# signalIsolator.net
KiCad netlist of a schematic drawn in Altium Designer
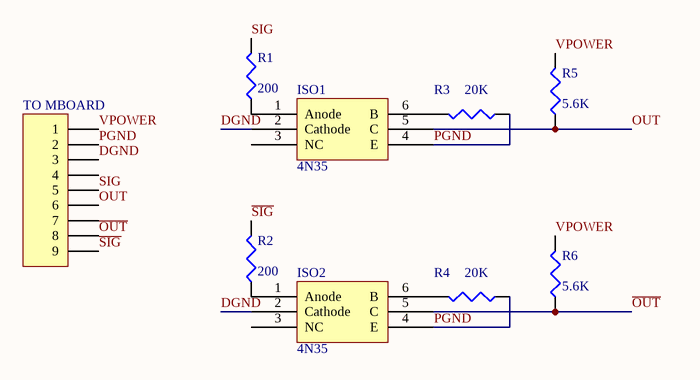
[diagram p0: signalIsolator.SchDoc]

(export (version "E")
  (design (tool "Eeschema 10.0.6"))
  (components
    (comp (ref "ISO1")
      (value "4N35")
      (footprint "DIP6LGE")
      (libsource (lib "controllerSchLib") (part "4N35"))
    )
    (comp (ref "ISO2")
      (value "4N35")
      (footprint "DIP6LGE")
      (libsource (lib "controllerSchLib") (part "4N35"))
    )
    (comp (ref "R1")
      (value "200")
      (footprint "Res10mm_LGE1.0")
      (description "resistor (specify value)")
      (fields (field (name "Comment") "-Res") (field (name "PUBLISHER") "Altium Limited"))
      (libsource (lib "PartsDatabaseV13p1") (part "G-Res"))
    )
    (comp (ref "R2")
      (value "200")
      (footprint "Res10mm_LGE1.0")
      (description "resistor (specify value)")
      (fields (field (name "PUBLISHER") "Altium Limited"))
      (libsource (lib "PartsDatabaseV13p1") (part "G-Res"))
    )
    (comp (ref "R3")
      (value "20K")
      (footprint "Res10mm_LGE1.0")
      (description "resistor (specify value)")
      (fields (field (name "Comment") "G-Res") (field (name "PUBLISHER") "Altium Limited"))
      (libsource (lib "PartsDatabaseV13p1") (part "G-Res"))
    )
    (comp (ref "R4")
      (value "20K")
      (footprint "Res10mm_LGE1.0")
      (description "resistor (specify value)")
      (fields (field (name "Comment") "G-Res") (field (name "PUBLISHER") "Altium Limited"))
      (libsource (lib "PartsDatabaseV13p1") (part "G-Res"))
    )
    (comp (ref "R5")
      (value "5.6K")
      (footprint "Res10mm_LGE1.0")
      (description "resistor (specify value)")
      (fields (field (name "Comment") "G-Res") (field (name "PUBLISHER") "Altium Limited"))
      (libsource (lib "PartsDatabaseV13p1") (part "G-Res"))
    )
    (comp (ref "R6")
      (value "5.6K")
      (footprint "Res10mm_LGE1.0")
      (description "resistor (specify value)")
      (fields (field (name "Comment") "G-Res") (field (name "PUBLISHER") "Altium Limited"))
      (libsource (lib "PartsDatabaseV13p1") (part "G-Res"))
    )
    (comp (ref "TO MBOARD")
      (value "~")
      (footprint "HDR1X9_LGE1.0")
      (description "Header, 10-Pin")
      (fields (field (name "PUBLISHER") "Altium Limited"))
      (libsource (lib "PartsDatabaseV13p1") (part "C-Hdr1x9"))
    )
  )
  (nets
    (net (code "1") (name "/DGND") (class "Default")
      (node (ref "ISO1") (pin "2") (pinfunction "Cathode_2") (pintype "passive"))
      (node (ref "ISO2") (pin "2") (pinfunction "Cathode_2") (pintype "passive"))
      (node (ref "TO MBOARD") (pin "3") (pinfunction "3_3") (pintype "passive"))
    )
    (net (code "2") (name "/OUT") (class "Default")
      (node (ref "ISO1") (pin "5") (pinfunction "C_5") (pintype "passive"))
      (node (ref "R5") (pin "1") (pinfunction "1_1") (pintype "passive"))
      (node (ref "TO MBOARD") (pin "6") (pinfunction "6_6") (pintype "passive"))
    )
    (net (code "3") (name "/PGND") (class "Default")
      (node (ref "ISO1") (pin "4") (pinfunction "E_4") (pintype "passive"))
      (node (ref "ISO2") (pin "4") (pinfunction "E_4") (pintype "passive"))
      (node (ref "R3") (pin "1") (pinfunction "1_1") (pintype "passive"))
      (node (ref "R4") (pin "1") (pinfunction "1_1") (pintype "passive"))
      (node (ref "TO MBOARD") (pin "2") (pinfunction "2_2") (pintype "passive"))
    )
    (net (code "4") (name "/SIG") (class "Default")
      (node (ref "R1") (pin "2") (pinfunction "2_2") (pintype "passive"))
      (node (ref "TO MBOARD") (pin "5") (pinfunction "5_5") (pintype "passive"))
    )
    (net (code "5") (name "/VPOWER") (class "Default")
      (node (ref "R5") (pin "2") (pinfunction "2_2") (pintype "passive"))
      (node (ref "R6") (pin "2") (pinfunction "2_2") (pintype "passive"))
      (node (ref "TO MBOARD") (pin "1") (pinfunction "1_1") (pintype "passive"))
    )
    (net (code "6") (name "/~{OUT}") (class "Default")
      (node (ref "ISO2") (pin "5") (pinfunction "C_5") (pintype "passive"))
      (node (ref "R6") (pin "1") (pinfunction "1_1") (pintype "passive"))
      (node (ref "TO MBOARD") (pin "8") (pinfunction "8_8") (pintype "passive"))
    )
    (net (code "7") (name "/~{SIG}") (class "Default")
      (node (ref "R2") (pin "2") (pinfunction "2_2") (pintype "passive"))
      (node (ref "TO MBOARD") (pin "9") (pinfunction "9_9") (pintype "passive"))
    )
    (net (code "8") (name "Net-(ISO1-Anode)") (class "Default")
      (node (ref "ISO1") (pin "1") (pinfunction "Anode_1") (pintype "passive"))
      (node (ref "R1") (pin "1") (pinfunction "1_1") (pintype "passive"))
    )
    (net (code "9") (name "Net-(ISO1-B)") (class "Default")
      (node (ref "ISO1") (pin "6") (pinfunction "B_6") (pintype "passive"))
      (node (ref "R3") (pin "2") (pinfunction "2_2") (pintype "passive"))
    )
    (net (code "10") (name "Net-(ISO2-Anode)") (class "Default")
      (node (ref "ISO2") (pin "1") (pinfunction "Anode_1") (pintype "passive"))
      (node (ref "R2") (pin "1") (pinfunction "1_1") (pintype "passive"))
    )
    (net (code "11") (name "Net-(ISO2-B)") (class "Default")
      (node (ref "ISO2") (pin "6") (pinfunction "B_6") (pintype "passive"))
      (node (ref "R4") (pin "2") (pinfunction "2_2") (pintype "passive"))
    )
    (net (code "12") (name "unconnected-(ISO1-NC-Pad3)") (class "Default")
      (node (ref "ISO1") (pin "3") (pinfunction "NC_3") (pintype "passive"))
    )
    (net (code "13") (name "unconnected-(ISO2-NC-Pad3)") (class "Default")
      (node (ref "ISO2") (pin "3") (pinfunction "NC_3") (pintype "passive"))
    )
    (net (code "14") (name "unconnected-(TO MBOARD-Pad4)") (class "Default")
      (node (ref "TO MBOARD") (pin "4") (pinfunction "4_4") (pintype "passive"))
    )
    (net (code "15") (name "unconnected-(TO MBOARD-Pad7)") (class "Default")
      (node (ref "TO MBOARD") (pin "7") (pinfunction "7_7") (pintype "passive"))
    )
  )
)
